# Cargador_RasPi3HAT_CamSlot_v1_3.net
KiCad netlist of a schematic drawn in EAGLE
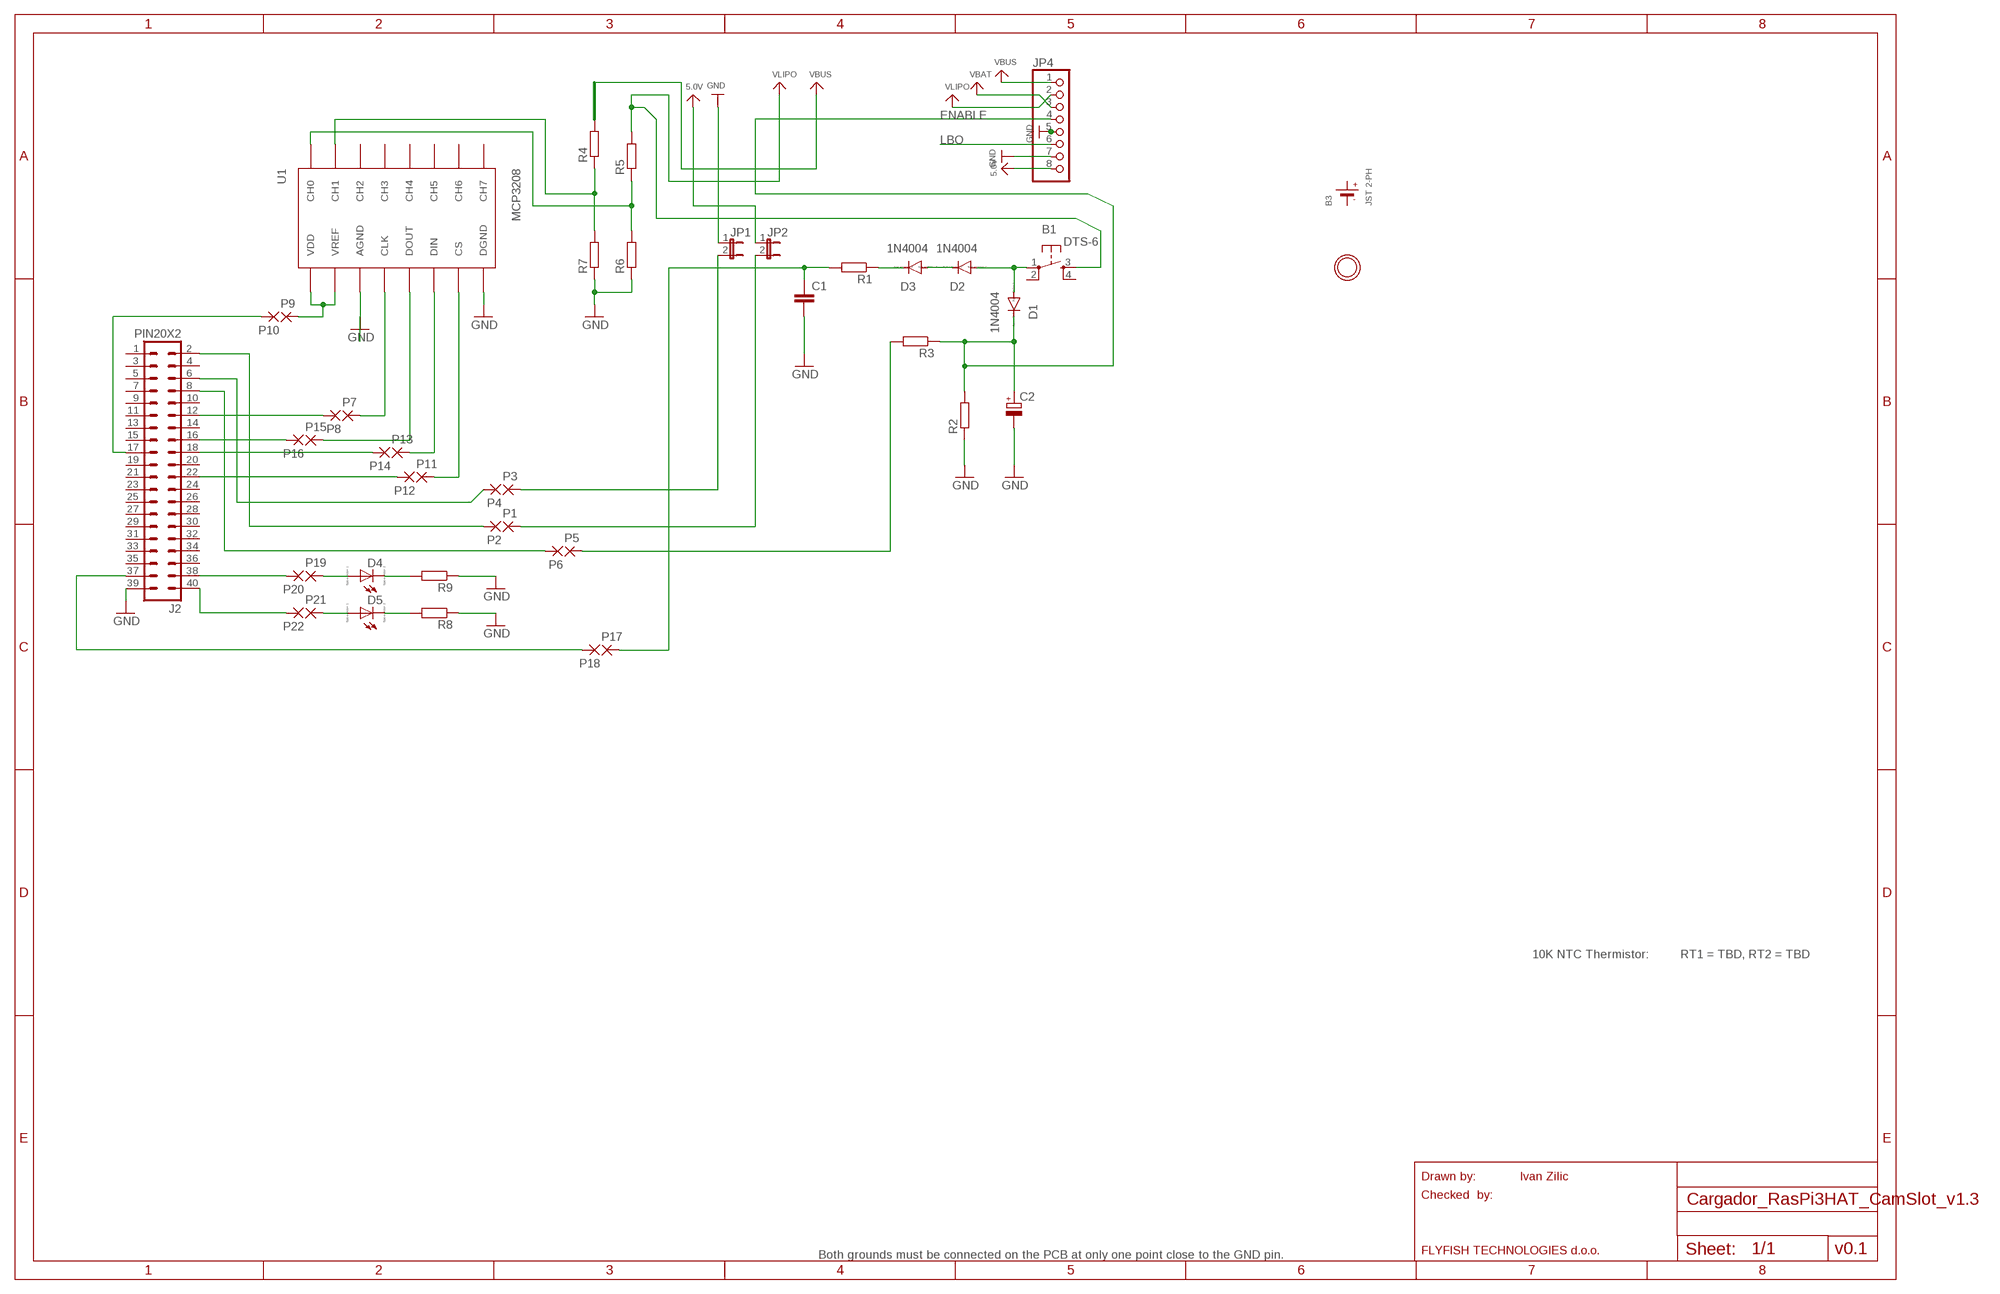
[diagram p0: schematic, sheet 1]

(export (version "E")
  (design (tool "Eeschema 10.0.6"))
  (components
    (comp (ref "B1")
      (value "DTS-6")
      (footprint "eagle-import:DTS-6")
      (libsource (lib "eagle-import") (part "DTS-6"))
    )
    (comp (ref "B3")
      (value "JST 2-PH")
      (footprint "eagle-import:JSTPH2")
      (libsource (lib "eagle-import") (part "BATTERY"))
    )
    (comp (ref "C1")
      (value "C2.5/2")
      (footprint "eagle-import:C2.5-2")
      (libsource (lib "eagle-import") (part "C2.5/2"))
    )
    (comp (ref "C2")
      (value "CPOL-EUE5-4")
      (footprint "eagle-import:E5-4")
      (libsource (lib "eagle-import") (part "CPOL-EUE5-4"))
    )
    (comp (ref "D1")
      (value "1N4004")
      (footprint "eagle-import:DO41-10")
      (libsource (lib "eagle-import") (part "1N4004"))
    )
    (comp (ref "D2")
      (value "1N4004")
      (footprint "eagle-import:DO41-10")
      (libsource (lib "eagle-import") (part "1N4004"))
    )
    (comp (ref "D3")
      (value "1N4004")
      (footprint "eagle-import:DO41-10")
      (libsource (lib "eagle-import") (part "1N4004"))
    )
    (comp (ref "D4")
      (value "LED_ELD260")
      (footprint "eagle-import:LED_LD260")
      (libsource (lib "eagle-import") (part "LED_ELD260"))
    )
    (comp (ref "D5")
      (value "LED_ELD260")
      (footprint "eagle-import:LED_LD260")
      (libsource (lib "eagle-import") (part "LED_ELD260"))
    )
    (comp (ref "J2")
      (value "PIN20X2")
      (footprint "eagle-import:PIN_20X2")
      (libsource (lib "eagle-import") (part "PIN20X2"))
    )
    (comp (ref "JP1")
      (value "JP1E")
      (footprint "eagle-import:JP1")
      (libsource (lib "eagle-import") (part "JP1E"))
    )
    (comp (ref "JP2")
      (value "JP1E")
      (footprint "eagle-import:JP1")
      (libsource (lib "eagle-import") (part "JP1E"))
    )
    (comp (ref "JP4")
      (value "HEADER-1X8")
      (footprint "eagle-import:1X08_OVAL")
      (libsource (lib "eagle-import") (part "HEADER-1X8"))
    )
    (comp (ref "P1")
      (value "2,15/1,0")
      (footprint "eagle-import:2,15_1,0")
      (libsource (lib "eagle-import") (part "2,15/1,0"))
    )
    (comp (ref "P2")
      (value "2,15/1,0")
      (footprint "eagle-import:2,15_1,0")
      (libsource (lib "eagle-import") (part "2,15/1,0"))
    )
    (comp (ref "P3")
      (value "2,15/1,0")
      (footprint "eagle-import:2,15_1,0")
      (libsource (lib "eagle-import") (part "2,15/1,0"))
    )
    (comp (ref "P4")
      (value "2,15/1,0")
      (footprint "eagle-import:2,15_1,0")
      (libsource (lib "eagle-import") (part "2,15/1,0"))
    )
    (comp (ref "P5")
      (value "2,15/1,0")
      (footprint "eagle-import:2,15_1,0")
      (libsource (lib "eagle-import") (part "2,15/1,0"))
    )
    (comp (ref "P6")
      (value "2,15/1,0")
      (footprint "eagle-import:2,15_1,0")
      (libsource (lib "eagle-import") (part "2,15/1,0"))
    )
    (comp (ref "P7")
      (value "2,15/1,0")
      (footprint "eagle-import:2,15_1,0")
      (libsource (lib "eagle-import") (part "2,15/1,0"))
    )
    (comp (ref "P8")
      (value "2,15/1,0")
      (footprint "eagle-import:2,15_1,0")
      (libsource (lib "eagle-import") (part "2,15/1,0"))
    )
    (comp (ref "P9")
      (value "2,15/1,0")
      (footprint "eagle-import:2,15_1,0")
      (libsource (lib "eagle-import") (part "2,15/1,0"))
    )
    (comp (ref "P10")
      (value "2,15/1,0")
      (footprint "eagle-import:2,15_1,0")
      (libsource (lib "eagle-import") (part "2,15/1,0"))
    )
    (comp (ref "P11")
      (value "2,15/1,0")
      (footprint "eagle-import:2,15_1,0")
      (libsource (lib "eagle-import") (part "2,15/1,0"))
    )
    (comp (ref "P12")
      (value "2,15/1,0")
      (footprint "eagle-import:2,15_1,0")
      (libsource (lib "eagle-import") (part "2,15/1,0"))
    )
    (comp (ref "P13")
      (value "2,15/1,0")
      (footprint "eagle-import:2,15_1,0")
      (libsource (lib "eagle-import") (part "2,15/1,0"))
    )
    (comp (ref "P14")
      (value "2,15/1,0")
      (footprint "eagle-import:2,15_1,0")
      (libsource (lib "eagle-import") (part "2,15/1,0"))
    )
    (comp (ref "P15")
      (value "2,15/1,0")
      (footprint "eagle-import:2,15_1,0")
      (libsource (lib "eagle-import") (part "2,15/1,0"))
    )
    (comp (ref "P16")
      (value "2,15/1,0")
      (footprint "eagle-import:2,15_1,0")
      (libsource (lib "eagle-import") (part "2,15/1,0"))
    )
    (comp (ref "P17")
      (value "2,15/1,0")
      (footprint "eagle-import:2,15_1,0")
      (libsource (lib "eagle-import") (part "2,15/1,0"))
    )
    (comp (ref "P18")
      (value "2,15/1,0")
      (footprint "eagle-import:2,15_1,0")
      (libsource (lib "eagle-import") (part "2,15/1,0"))
    )
    (comp (ref "P19")
      (value "2,15/1,0")
      (footprint "eagle-import:2,15_1,0")
      (libsource (lib "eagle-import") (part "2,15/1,0"))
    )
    (comp (ref "P20")
      (value "2,15/1,0")
      (footprint "eagle-import:2,15_1,0")
      (libsource (lib "eagle-import") (part "2,15/1,0"))
    )
    (comp (ref "P21")
      (value "2,15/1,0")
      (footprint "eagle-import:2,15_1,0")
      (libsource (lib "eagle-import") (part "2,15/1,0"))
    )
    (comp (ref "P22")
      (value "2,15/1,0")
      (footprint "eagle-import:2,15_1,0")
      (libsource (lib "eagle-import") (part "2,15/1,0"))
    )
    (comp (ref "R1")
      (value "R-EU_0207/10")
      (footprint "eagle-import:0207_10")
      (libsource (lib "eagle-import") (part "R-EU_0207/10"))
    )
    (comp (ref "R2")
      (value "R-EU_0207/10")
      (footprint "eagle-import:0207_10")
      (libsource (lib "eagle-import") (part "R-EU_0207/10"))
    )
    (comp (ref "R3")
      (value "R-EU_0207/10")
      (footprint "eagle-import:0207_10")
      (libsource (lib "eagle-import") (part "R-EU_0207/10"))
    )
    (comp (ref "R4")
      (value "R-EU_0207/10")
      (footprint "eagle-import:0207_10")
      (libsource (lib "eagle-import") (part "R-EU_0207/10"))
    )
    (comp (ref "R5")
      (value "R-EU_0207/10")
      (footprint "eagle-import:0207_10")
      (libsource (lib "eagle-import") (part "R-EU_0207/10"))
    )
    (comp (ref "R6")
      (value "R-EU_0207/10")
      (footprint "eagle-import:0207_10")
      (libsource (lib "eagle-import") (part "R-EU_0207/10"))
    )
    (comp (ref "R7")
      (value "R-EU_0207/10")
      (footprint "eagle-import:0207_10")
      (libsource (lib "eagle-import") (part "R-EU_0207/10"))
    )
    (comp (ref "R8")
      (value "R-EU_0207/10")
      (footprint "eagle-import:0207_10")
      (libsource (lib "eagle-import") (part "R-EU_0207/10"))
    )
    (comp (ref "R9")
      (value "R-EU_0207/10")
      (footprint "eagle-import:0207_10")
      (libsource (lib "eagle-import") (part "R-EU_0207/10"))
    )
    (comp (ref "U$5")
      (value "MOUNTINGHOLE2.5")
      (footprint "eagle-import:MOUNTINGHOLE_2.5_PLATED")
      (libsource (lib "eagle-import") (part "MOUNTINGHOLE2.5"))
    )
    (comp (ref "U1")
      (value "MCP3208")
      (footprint "eagle-import:DIL16")
      (libsource (lib "eagle-import") (part "MCP3208"))
    )
  )
  (nets
    (net (code "1") (name "/ENABLE") (class "Default")
      (node (ref "C2") (pin "+") (pinfunction "+_+") (pintype "passive"))
      (node (ref "D1") (pin "C") (pinfunction "C_C") (pintype "passive"))
      (node (ref "JP4") (pin "4") (pinfunction "4_4") (pintype "passive"))
      (node (ref "R2") (pin "2") (pinfunction "2_2") (pintype "passive"))
      (node (ref "R3") (pin "1") (pinfunction "1_1") (pintype "passive"))
    )
    (net (code "2") (name "/LBO") (class "Default")
      (node (ref "JP4") (pin "6") (pinfunction "6_6") (pintype "passive"))
    )
    (net (code "3") (name "5.0V") (class "Default")
      (node (ref "JP2") (pin "1") (pinfunction "1_1") (pintype "passive"))
      (node (ref "JP4") (pin "8") (pinfunction "8_8") (pintype "passive"))
    )
    (net (code "4") (name "GND") (class "Default")
      (node (ref "C1") (pin "2") (pinfunction "2_2") (pintype "passive"))
      (node (ref "C2") (pin "-") (pinfunction "-_-") (pintype "passive"))
      (node (ref "J2") (pin "39") (pinfunction "39_39") (pintype "passive"))
      (node (ref "JP1") (pin "1") (pinfunction "1_1") (pintype "passive"))
      (node (ref "JP4") (pin "5") (pinfunction "5_5") (pintype "passive"))
      (node (ref "JP4") (pin "7") (pinfunction "7_7") (pintype "passive"))
      (node (ref "R2") (pin "1") (pinfunction "1_1") (pintype "passive"))
      (node (ref "R6") (pin "1") (pinfunction "1_1") (pintype "passive"))
      (node (ref "R7") (pin "1") (pinfunction "1_1") (pintype "passive"))
      (node (ref "R8") (pin "1") (pinfunction "1_1") (pintype "passive"))
      (node (ref "R9") (pin "1") (pinfunction "1_1") (pintype "passive"))
      (node (ref "U1") (pin "AGND") (pinfunction "AGND_AGND") (pintype "power_in"))
      (node (ref "U1") (pin "DGND") (pinfunction "DGND_DGND") (pintype "power_in"))
    )
    (net (code "5") (name "Net-(B1-Pad1)") (class "Default")
      (node (ref "B1") (pin "1") (pinfunction "1_1") (pintype "passive"))
      (node (ref "D1") (pin "A") (pinfunction "A_A") (pintype "passive"))
      (node (ref "D2") (pin "A") (pinfunction "A_A") (pintype "passive"))
    )
    (net (code "6") (name "Net-(D2-PadC)") (class "Default")
      (node (ref "D2") (pin "C") (pinfunction "C_C") (pintype "passive"))
      (node (ref "D3") (pin "A") (pinfunction "A_A") (pintype "passive"))
    )
    (net (code "7") (name "Net-(D3-PadC)") (class "Default")
      (node (ref "D3") (pin "C") (pinfunction "C_C") (pintype "passive"))
      (node (ref "R1") (pin "1") (pinfunction "1_1") (pintype "passive"))
    )
    (net (code "8") (name "Net-(D4-C)") (class "Default")
      (node (ref "D4") (pin "K") (pinfunction "C_K") (pintype "passive"))
      (node (ref "R9") (pin "2") (pinfunction "2_2") (pintype "passive"))
    )
    (net (code "9") (name "Net-(D5-C)") (class "Default")
      (node (ref "D5") (pin "K") (pinfunction "C_K") (pintype "passive"))
      (node (ref "R8") (pin "2") (pinfunction "2_2") (pintype "passive"))
    )
    (net (code "10") (name "Net-(P1-P)") (class "Default")
      (node (ref "JP2") (pin "2") (pinfunction "2_2") (pintype "passive"))
      (node (ref "P1") (pin "1") (pinfunction "P_1") (pintype "passive"))
    )
    (net (code "11") (name "Net-(P2-P)") (class "Default")
      (node (ref "J2") (pin "2") (pinfunction "2_2") (pintype "passive"))
      (node (ref "P2") (pin "1") (pinfunction "P_1") (pintype "passive"))
    )
    (net (code "12") (name "Net-(P3-P)") (class "Default")
      (node (ref "JP1") (pin "2") (pinfunction "2_2") (pintype "passive"))
      (node (ref "P3") (pin "1") (pinfunction "P_1") (pintype "passive"))
    )
    (net (code "13") (name "Net-(P4-P)") (class "Default")
      (node (ref "J2") (pin "6") (pinfunction "6_6") (pintype "passive"))
      (node (ref "P4") (pin "1") (pinfunction "P_1") (pintype "passive"))
    )
    (net (code "14") (name "Net-(P5-P)") (class "Default")
      (node (ref "P5") (pin "1") (pinfunction "P_1") (pintype "passive"))
      (node (ref "R3") (pin "2") (pinfunction "2_2") (pintype "passive"))
    )
    (net (code "15") (name "Net-(P6-P)") (class "Default")
      (node (ref "J2") (pin "8") (pinfunction "8_8") (pintype "passive"))
      (node (ref "P6") (pin "1") (pinfunction "P_1") (pintype "passive"))
    )
    (net (code "16") (name "Net-(P7-P)") (class "Default")
      (node (ref "P7") (pin "1") (pinfunction "P_1") (pintype "passive"))
      (node (ref "U1") (pin "CLK") (pinfunction "CLK_CLK") (pintype "input"))
    )
    (net (code "17") (name "Net-(P8-P)") (class "Default")
      (node (ref "J2") (pin "12") (pinfunction "12_12") (pintype "passive"))
      (node (ref "P8") (pin "1") (pinfunction "P_1") (pintype "passive"))
    )
    (net (code "18") (name "Net-(P9-P)") (class "Default")
      (node (ref "P9") (pin "1") (pinfunction "P_1") (pintype "passive"))
      (node (ref "U1") (pin "VDD") (pinfunction "VDD_VDD") (pintype "power_in"))
      (node (ref "U1") (pin "VREF") (pinfunction "VREF_VREF") (pintype "input"))
    )
    (net (code "19") (name "Net-(P10-P)") (class "Default")
      (node (ref "J2") (pin "17") (pinfunction "17_17") (pintype "passive"))
      (node (ref "P10") (pin "1") (pinfunction "P_1") (pintype "passive"))
    )
    (net (code "20") (name "Net-(P11-P)") (class "Default")
      (node (ref "P11") (pin "1") (pinfunction "P_1") (pintype "passive"))
      (node (ref "U1") (pin "CS") (pinfunction "CS_CS") (pintype "input"))
    )
    (net (code "21") (name "Net-(P12-P)") (class "Default")
      (node (ref "J2") (pin "22") (pinfunction "22_22") (pintype "passive"))
      (node (ref "P12") (pin "1") (pinfunction "P_1") (pintype "passive"))
    )
    (net (code "22") (name "Net-(P13-P)") (class "Default")
      (node (ref "P13") (pin "1") (pinfunction "P_1") (pintype "passive"))
      (node (ref "U1") (pin "DIN") (pinfunction "DIN_DIN") (pintype "input"))
    )
    (net (code "23") (name "Net-(P14-P)") (class "Default")
      (node (ref "J2") (pin "18") (pinfunction "18_18") (pintype "passive"))
      (node (ref "P14") (pin "1") (pinfunction "P_1") (pintype "passive"))
    )
    (net (code "24") (name "Net-(P15-P)") (class "Default")
      (node (ref "P15") (pin "1") (pinfunction "P_1") (pintype "passive"))
      (node (ref "U1") (pin "DOUT") (pinfunction "DOUT_DOUT") (pintype "output"))
    )
    (net (code "25") (name "Net-(P16-P)") (class "Default")
      (node (ref "J2") (pin "16") (pinfunction "16_16") (pintype "passive"))
      (node (ref "P16") (pin "1") (pinfunction "P_1") (pintype "passive"))
    )
    (net (code "26") (name "Net-(P17-P)") (class "Default")
      (node (ref "C1") (pin "1") (pinfunction "1_1") (pintype "passive"))
      (node (ref "P17") (pin "1") (pinfunction "P_1") (pintype "passive"))
      (node (ref "R1") (pin "2") (pinfunction "2_2") (pintype "passive"))
    )
    (net (code "27") (name "Net-(P18-P)") (class "Default")
      (node (ref "J2") (pin "37") (pinfunction "37_37") (pintype "passive"))
      (node (ref "P18") (pin "1") (pinfunction "P_1") (pintype "passive"))
    )
    (net (code "28") (name "Net-(P19-P)") (class "Default")
      (node (ref "D4") (pin "A") (pinfunction "A_A") (pintype "passive"))
      (node (ref "P19") (pin "1") (pinfunction "P_1") (pintype "passive"))
    )
    (net (code "29") (name "Net-(P20-P)") (class "Default")
      (node (ref "J2") (pin "38") (pinfunction "38_38") (pintype "passive"))
      (node (ref "P20") (pin "1") (pinfunction "P_1") (pintype "passive"))
    )
    (net (code "30") (name "Net-(P21-P)") (class "Default")
      (node (ref "D5") (pin "A") (pinfunction "A_A") (pintype "passive"))
      (node (ref "P21") (pin "1") (pinfunction "P_1") (pintype "passive"))
    )
    (net (code "31") (name "Net-(P22-P)") (class "Default")
      (node (ref "J2") (pin "40") (pinfunction "40_40") (pintype "passive"))
      (node (ref "P22") (pin "1") (pinfunction "P_1") (pintype "passive"))
    )
    (net (code "32") (name "Net-(R4-Pad1)") (class "Default")
      (node (ref "R4") (pin "1") (pinfunction "1_1") (pintype "passive"))
      (node (ref "R7") (pin "2") (pinfunction "2_2") (pintype "passive"))
      (node (ref "U1") (pin "CH1") (pinfunction "CH1_CH1") (pintype "input"))
    )
    (net (code "33") (name "Net-(R5-Pad1)") (class "Default")
      (node (ref "R5") (pin "1") (pinfunction "1_1") (pintype "passive"))
      (node (ref "R6") (pin "2") (pinfunction "2_2") (pintype "passive"))
      (node (ref "U1") (pin "CH0") (pinfunction "CH0_CH0") (pintype "input"))
    )
    (net (code "34") (name "VBAT") (class "Default")
      (node (ref "JP4") (pin "3") (pinfunction "3_3") (pintype "passive"))
    )
    (net (code "35") (name "VBUS") (class "Default")
      (node (ref "JP4") (pin "1") (pinfunction "1_1") (pintype "passive"))
      (node (ref "R4") (pin "2") (pinfunction "2_2") (pintype "passive"))
    )
    (net (code "36") (name "VLIPO") (class "Default")
      (node (ref "B1") (pin "3") (pinfunction "3_3") (pintype "passive"))
      (node (ref "JP4") (pin "2") (pinfunction "2_2") (pintype "passive"))
      (node (ref "R5") (pin "2") (pinfunction "2_2") (pintype "passive"))
    )
    (net (code "37") (name "unconnected-(B1-Pad2)") (class "Default")
      (node (ref "B1") (pin "2") (pinfunction "2_2") (pintype "passive"))
    )
    (net (code "38") (name "unconnected-(B1-Pad4)") (class "Default")
      (node (ref "B1") (pin "4") (pinfunction "4_4") (pintype "passive"))
    )
    (net (code "39") (name "unconnected-(B3-+-Pad2)") (class "Default")
      (node (ref "B3") (pin "2") (pinfunction "+_2") (pintype "passive"))
    )
    (net (code "40") (name "unconnected-(B3---Pad1)") (class "Default")
      (node (ref "B3") (pin "1") (pinfunction "-_1") (pintype "passive"))
    )
    (net (code "41") (name "unconnected-(J2-Pad1)") (class "Default")
      (node (ref "J2") (pin "1") (pinfunction "1_1") (pintype "passive"))
    )
    (net (code "42") (name "unconnected-(J2-Pad3)") (class "Default")
      (node (ref "J2") (pin "3") (pinfunction "3_3") (pintype "passive"))
    )
    (net (code "43") (name "unconnected-(J2-Pad4)") (class "Default")
      (node (ref "J2") (pin "4") (pinfunction "4_4") (pintype "passive"))
    )
    (net (code "44") (name "unconnected-(J2-Pad5)") (class "Default")
      (node (ref "J2") (pin "5") (pinfunction "5_5") (pintype "passive"))
    )
    (net (code "45") (name "unconnected-(J2-Pad7)") (class "Default")
      (node (ref "J2") (pin "7") (pinfunction "7_7") (pintype "passive"))
    )
    (net (code "46") (name "unconnected-(J2-Pad9)") (class "Default")
      (node (ref "J2") (pin "9") (pinfunction "9_9") (pintype "passive"))
    )
    (net (code "47") (name "unconnected-(J2-Pad10)") (class "Default")
      (node (ref "J2") (pin "10") (pinfunction "10_10") (pintype "passive"))
    )
    (net (code "48") (name "unconnected-(J2-Pad11)") (class "Default")
      (node (ref "J2") (pin "11") (pinfunction "11_11") (pintype "passive"))
    )
    (net (code "49") (name "unconnected-(J2-Pad13)") (class "Default")
      (node (ref "J2") (pin "13") (pinfunction "13_13") (pintype "passive"))
    )
    (net (code "50") (name "unconnected-(J2-Pad14)") (class "Default")
      (node (ref "J2") (pin "14") (pinfunction "14_14") (pintype "passive"))
    )
    (net (code "51") (name "unconnected-(J2-Pad15)") (class "Default")
      (node (ref "J2") (pin "15") (pinfunction "15_15") (pintype "passive"))
    )
    (net (code "52") (name "unconnected-(J2-Pad19)") (class "Default")
      (node (ref "J2") (pin "19") (pinfunction "19_19") (pintype "passive"))
    )
    (net (code "53") (name "unconnected-(J2-Pad20)") (class "Default")
      (node (ref "J2") (pin "20") (pinfunction "20_20") (pintype "passive"))
    )
    (net (code "54") (name "unconnected-(J2-Pad21)") (class "Default")
      (node (ref "J2") (pin "21") (pinfunction "21_21") (pintype "passive"))
    )
    (net (code "55") (name "unconnected-(J2-Pad23)") (class "Default")
      (node (ref "J2") (pin "23") (pinfunction "23_23") (pintype "passive"))
    )
    (net (code "56") (name "unconnected-(J2-Pad24)") (class "Default")
      (node (ref "J2") (pin "24") (pinfunction "24_24") (pintype "passive"))
    )
    (net (code "57") (name "unconnected-(J2-Pad25)") (class "Default")
      (node (ref "J2") (pin "25") (pinfunction "25_25") (pintype "passive"))
    )
    (net (code "58") (name "unconnected-(J2-Pad26)") (class "Default")
      (node (ref "J2") (pin "26") (pinfunction "26_26") (pintype "passive"))
    )
    (net (code "59") (name "unconnected-(J2-Pad27)") (class "Default")
      (node (ref "J2") (pin "27") (pinfunction "27_27") (pintype "passive"))
    )
    (net (code "60") (name "unconnected-(J2-Pad28)") (class "Default")
      (node (ref "J2") (pin "28") (pinfunction "28_28") (pintype "passive"))
    )
    (net (code "61") (name "unconnected-(J2-Pad29)") (class "Default")
      (node (ref "J2") (pin "29") (pinfunction "29_29") (pintype "passive"))
    )
    (net (code "62") (name "unconnected-(J2-Pad30)") (class "Default")
      (node (ref "J2") (pin "30") (pinfunction "30_30") (pintype "passive"))
    )
    (net (code "63") (name "unconnected-(J2-Pad31)") (class "Default")
      (node (ref "J2") (pin "31") (pinfunction "31_31") (pintype "passive"))
    )
    (net (code "64") (name "unconnected-(J2-Pad32)") (class "Default")
      (node (ref "J2") (pin "32") (pinfunction "32_32") (pintype "passive"))
    )
    (net (code "65") (name "unconnected-(J2-Pad33)") (class "Default")
      (node (ref "J2") (pin "33") (pinfunction "33_33") (pintype "passive"))
    )
    (net (code "66") (name "unconnected-(J2-Pad34)") (class "Default")
      (node (ref "J2") (pin "34") (pinfunction "34_34") (pintype "passive"))
    )
    (net (code "67") (name "unconnected-(J2-Pad35)") (class "Default")
      (node (ref "J2") (pin "35") (pinfunction "35_35") (pintype "passive"))
    )
    (net (code "68") (name "unconnected-(J2-Pad36)") (class "Default")
      (node (ref "J2") (pin "36") (pinfunction "36_36") (pintype "passive"))
    )
    (net (code "69") (name "unconnected-(U1-PadCH2)") (class "Default")
      (node (ref "U1") (pin "CH2") (pinfunction "CH2_CH2") (pintype "input"))
    )
    (net (code "70") (name "unconnected-(U1-PadCH3)") (class "Default")
      (node (ref "U1") (pin "CH3") (pinfunction "CH3_CH3") (pintype "input"))
    )
    (net (code "71") (name "unconnected-(U1-PadCH4)") (class "Default")
      (node (ref "U1") (pin "CH4") (pinfunction "CH4_CH4") (pintype "input"))
    )
    (net (code "72") (name "unconnected-(U1-PadCH5)") (class "Default")
      (node (ref "U1") (pin "CH5") (pinfunction "CH5_CH5") (pintype "input"))
    )
    (net (code "73") (name "unconnected-(U1-PadCH6)") (class "Default")
      (node (ref "U1") (pin "CH6") (pinfunction "CH6_CH6") (pintype "input"))
    )
    (net (code "74") (name "unconnected-(U1-PadCH7)") (class "Default")
      (node (ref "U1") (pin "CH7") (pinfunction "CH7_CH7") (pintype "input"))
    )
  )
)
